# schematic.net
KiCad netlist of a schematic drawn in EasyEDA
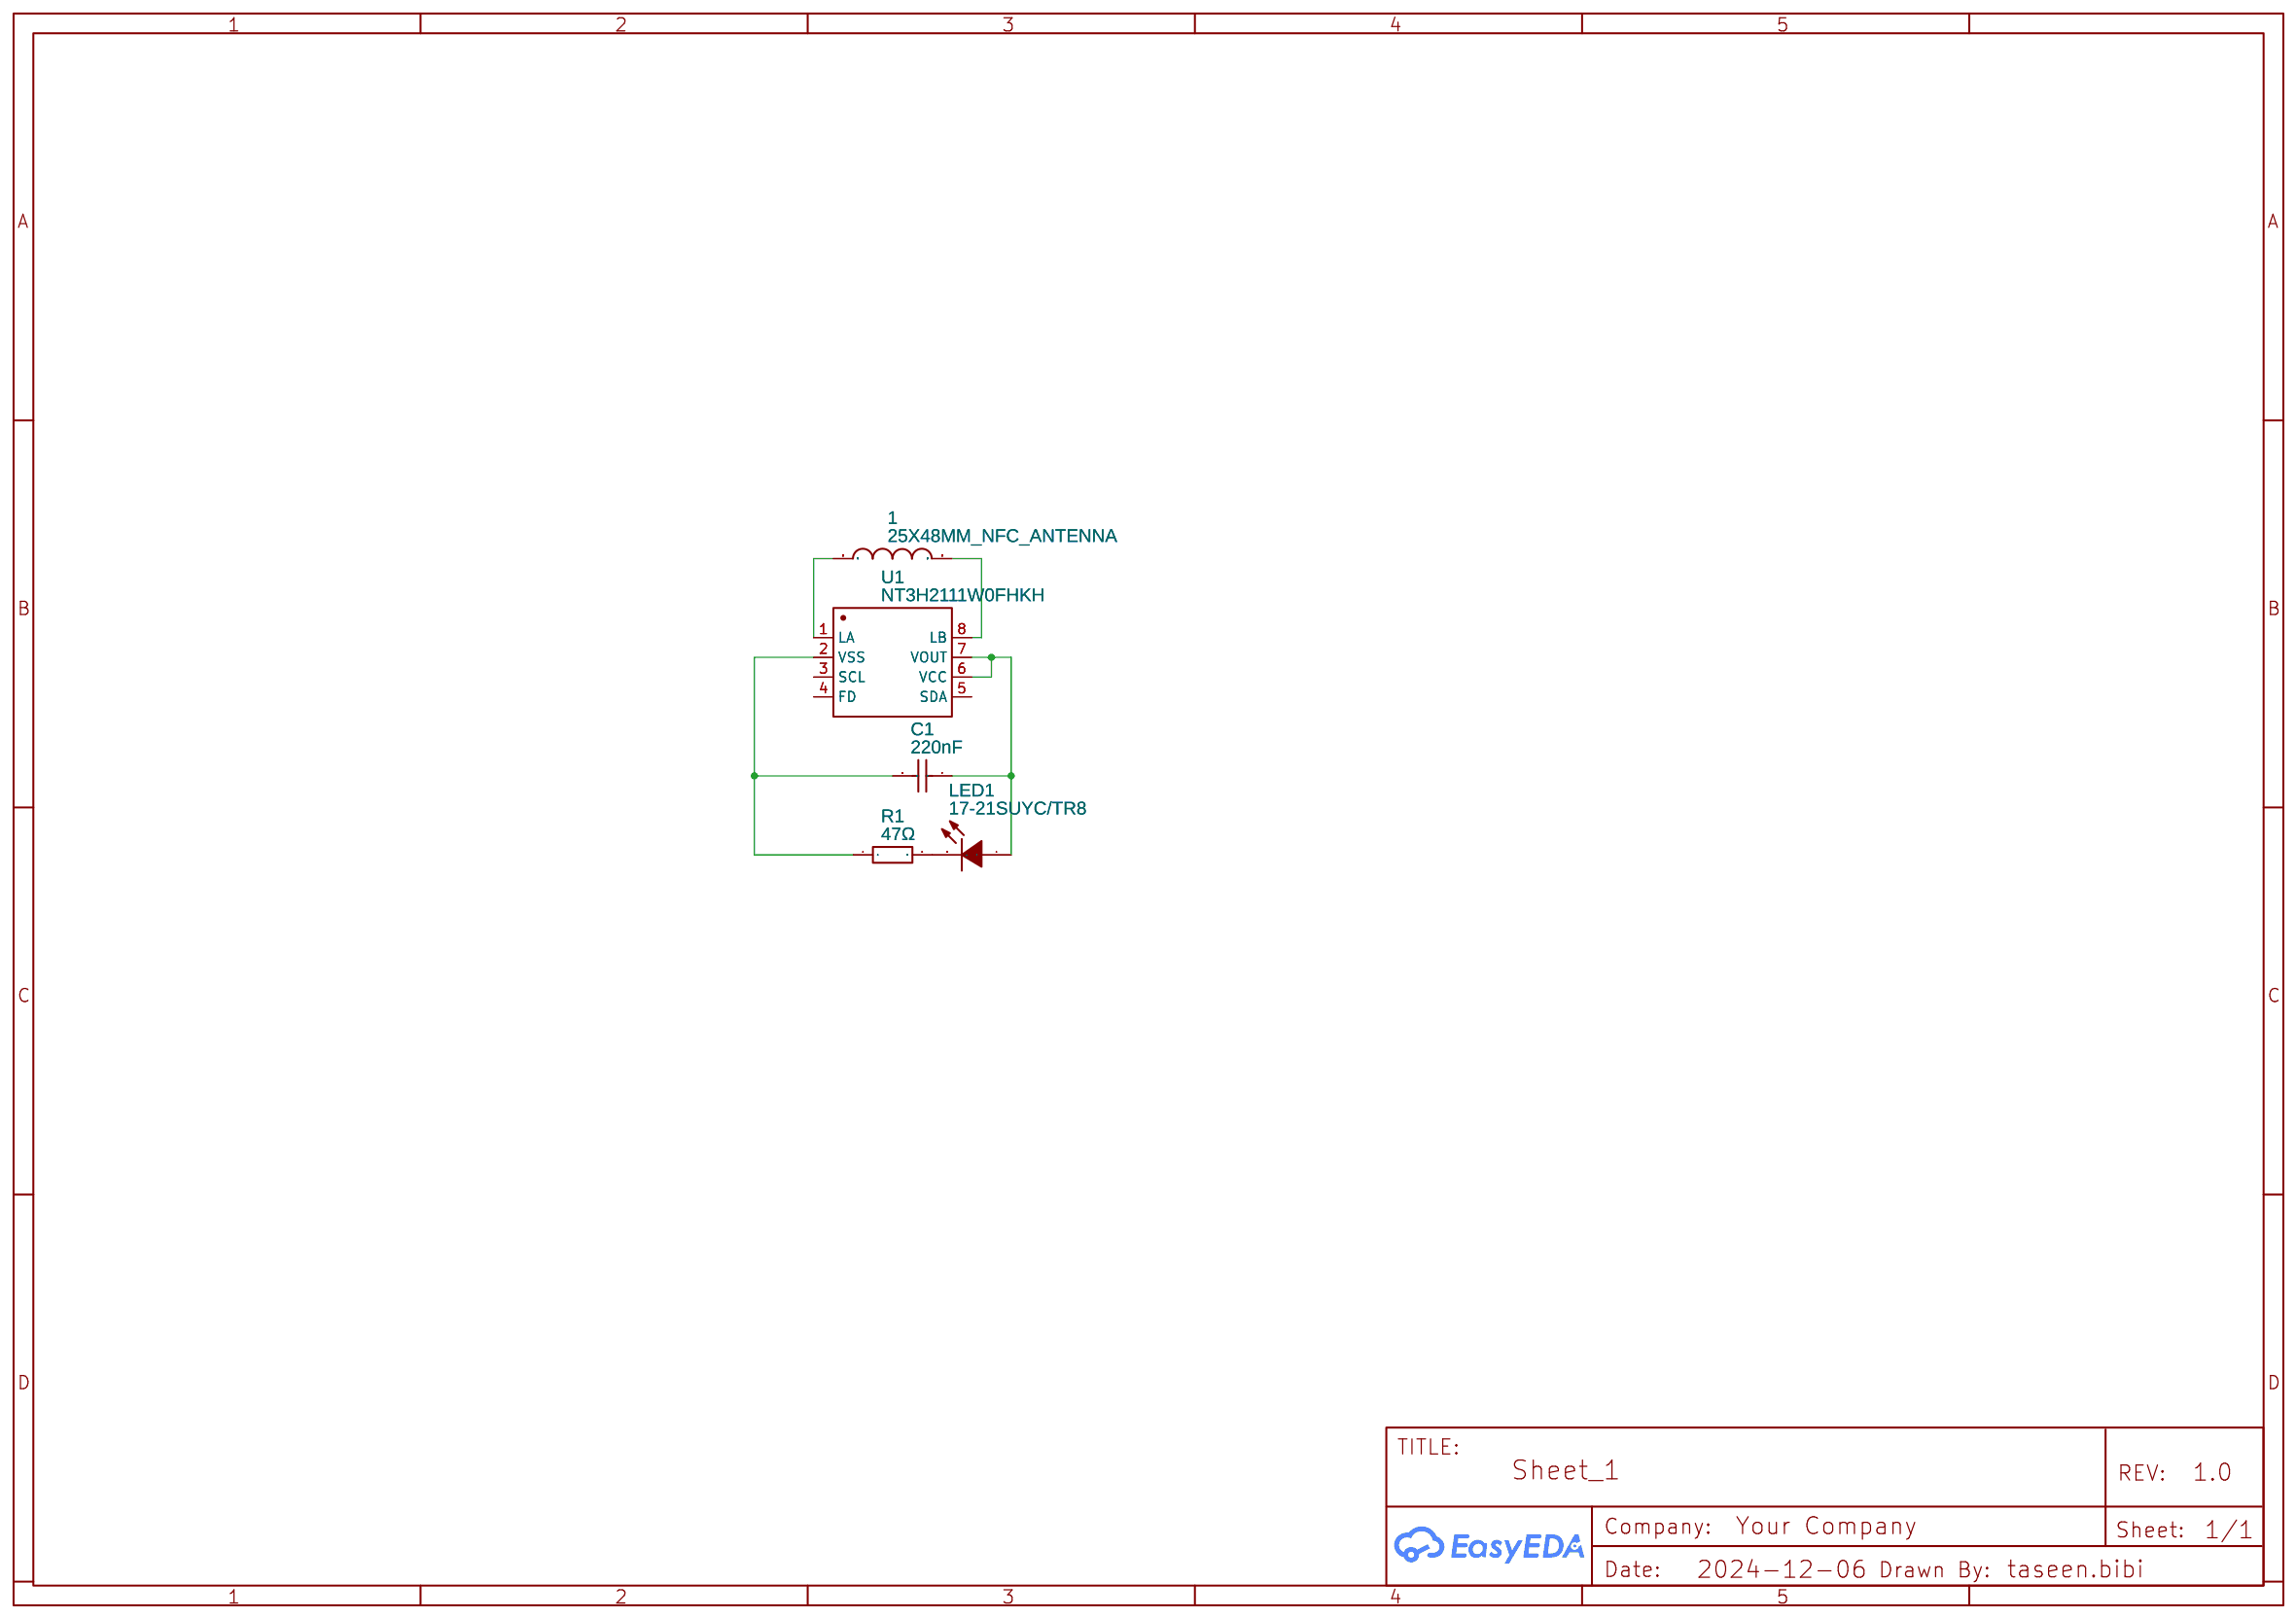
[diagram p0: schematic sheet]

(export (version "E")
  (design (tool "Eeschema 10.0.6"))
  (components
    (comp (ref "1") (value "25X48MM_NFC_ANTENNA") (libsource (lib "") (part "25X48MM_NFC_ANTENNA")))
    (comp (ref "C1")
      (value "220nF")
      (fields
        (field (name "Manufacturer Part") "CL10B224KA8NNNC")
        (field (name "Manufacturer") "SAMSUNG(三星)")
      )
      (libsource (lib "") (part "CL10B224KA8NNNC"))
    )
    (comp (ref "LED1")
      (value "17-21SUYC/TR8")
      (fields (field (name "Manufacturer Part") "KT-0805黄灯") (field (name "Manufacturer") "KENTO"))
      (libsource (lib "") (part "17-21SUYC/TR8"))
    )
    (comp (ref "R1")
      (value "47Ω")
      (fields
        (field (name "Manufacturer Part") "0603WAF470JT5E")
        (field (name "Manufacturer") "UNI-ROYAL(厚声)")
      )
      (libsource (lib "") (part "0603WAF470JT5E"))
    )
    (comp (ref "U1")
      (value "NT3H2111W0FHKH")
      (fields (field (name "Manufacturer") "NXP(恩智浦)"))
      (libsource (lib "") (part "NT3H2111W0FHKH"))
    )
  )
  (nets
    (net (code "1") (name "Net-(LED1-+)") (class "Default")
      (node (ref "C1") (pin "1") (pinfunction "1_1") (pintype "input"))
      (node (ref "LED1") (pin "1") (pinfunction "+_1") (pintype "unspecified"))
      (node (ref "U1") (pin "6") (pinfunction "VCC_6") (pintype "unspecified"))
      (node (ref "U1") (pin "7") (pinfunction "VOUT_7") (pintype "unspecified"))
    )
    (net (code "2") (name "Net-(LED1--)") (class "Default")
      (node (ref "LED1") (pin "2") (pinfunction "-_2") (pintype "unspecified"))
      (node (ref "R1") (pin "2") (pinfunction "2_2") (pintype "input"))
    )
    (net (code "3") (name "Net-(U1-LA)") (class "Default")
      (node (ref "1") (pin "P$1") (pinfunction "P$1_P$1") (pintype "bidirectional"))
      (node (ref "U1") (pin "1") (pinfunction "LA_1") (pintype "unspecified"))
    )
    (net (code "4") (name "Net-(U1-LB)") (class "Default")
      (node (ref "1") (pin "P$2") (pinfunction "P$2_P$2") (pintype "bidirectional"))
      (node (ref "U1") (pin "8") (pinfunction "LB_8") (pintype "unspecified"))
    )
    (net (code "5") (name "Net-(U1-VSS)") (class "Default")
      (node (ref "C1") (pin "2") (pinfunction "2_2") (pintype "input"))
      (node (ref "R1") (pin "1") (pinfunction "1_1") (pintype "input"))
      (node (ref "U1") (pin "2") (pinfunction "VSS_2") (pintype "unspecified"))
    )
    (net (code "6") (name "unconnected-(U1-FD-Pad4)") (class "Default")
      (node (ref "U1") (pin "4") (pinfunction "FD_4") (pintype "unspecified"))
    )
    (net (code "7") (name "unconnected-(U1-SCL-Pad3)") (class "Default")
      (node (ref "U1") (pin "3") (pinfunction "SCL_3") (pintype "unspecified"))
    )
    (net (code "8") (name "unconnected-(U1-SDA-Pad5)") (class "Default")
      (node (ref "U1") (pin "5") (pinfunction "SDA_5") (pintype "unspecified"))
    )
  )
)
